# E-26_Temp_Sensor.net
KiCad netlist of a schematic drawn in Altium Designer
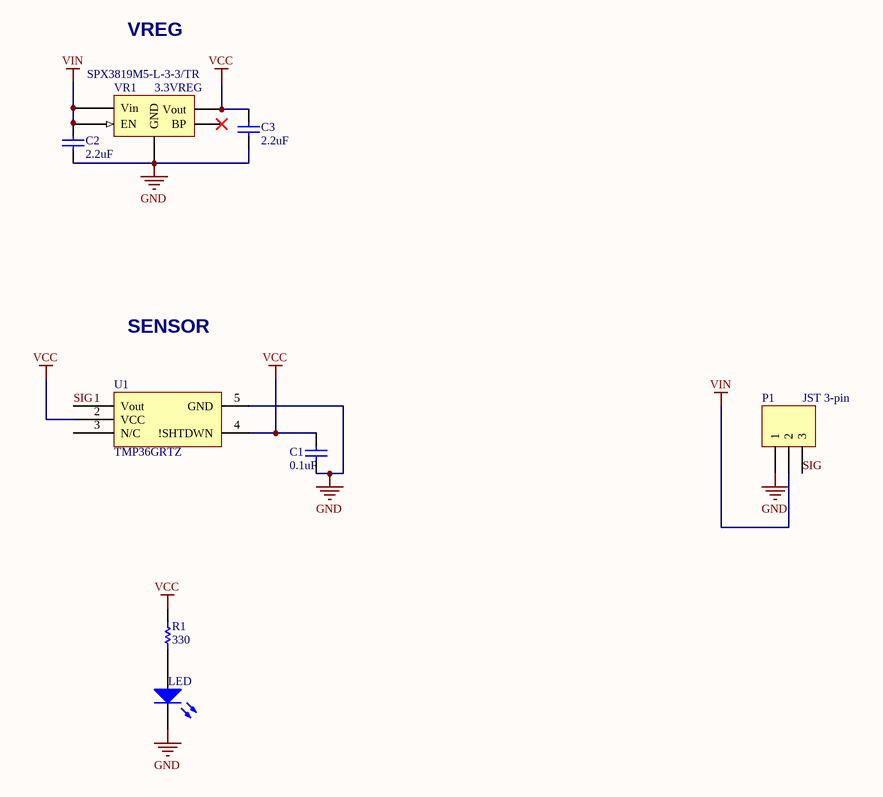
[diagram p0: E-26 Temp Sensor.SchDoc]

(export (version "E")
  (design (tool "Eeschema 10.0.6"))
  (components
    (comp (ref "C1")
      (value "0.1uF")
      (footprint "0805 TIGHT")
      (description "Capacitor")
      (fields (field (name "Comment") "18pF") (field (name "PUBLISHER") "Altium Limited"))
      (libsource (lib "SB_Discrete") (part "Cap"))
    )
    (comp (ref "C2")
      (value "2.2uF")
      (footprint "0805 TIGHT")
      (description "Capacitor")
      (fields (field (name "PUBLISHER") "Altium Limited"))
      (libsource (lib "SB_Discrete") (part "Cap"))
    )
    (comp (ref "C3")
      (value "2.2uF")
      (footprint "0805 TIGHT")
      (description "Capacitor")
      (fields (field (name "Comment") "100nF") (field (name "PUBLISHER") "Altium Limited"))
      (libsource (lib "SB_Discrete") (part "Cap"))
    )
    (comp (ref "LED")
      (value "LED2")
      (footprint "0805 LED - TIGHT")
      (description "Typical RED GaAs LED")
      (fields (field (name "PUBLISHER") "Altium Limited"))
      (libsource (lib "SB_Discrete") (part "LED1"))
    )
    (comp (ref "P1")
      (value "JST 3-pin")
      (footprint "JST-PH 3-pin SMD")
      (description "Header, 3-Pin")
      (fields (field (name "PUBLISHER") "Altium Limited"))
      (libsource (lib "Miscellaneous Connectors") (part "Header 3"))
    )
    (comp (ref "R1")
      (value "330")
      (footprint "0805 TIGHT")
      (description "Resistor")
      (fields (field (name "Comment") "Res1") (field (name "PUBLISHER") "Altium Limited"))
      (libsource (lib "SB_Discrete") (part "Res1"))
    )
    (comp (ref "U1")
      (value "TMP36GRTZ")
      (footprint "SOT-23-5")
      (libsource (lib "SB_Discrete") (part "TMP36"))
    )
    (comp (ref "VR1")
      (value "3.3VREG")
      (footprint "SOT-25 New")
      (libsource (lib "SB_Discrete") (part "Vreg SOT25"))
    )
  )
  (nets
    (net (code "1") (name "/SIG") (class "Default")
      (node (ref "P1") (pin "3") (pinfunction "3_3") (pintype "passive"))
      (node (ref "U1") (pin "1") (pinfunction "Vout_1") (pintype "power_in"))
    )
    (net (code "3") (name "GND") (class "Default")
      (node (ref "C1") (pin "1") (pinfunction "1_1") (pintype "passive"))
      (node (ref "C2") (pin "2") (pinfunction "2_2") (pintype "passive"))
      (node (ref "C3") (pin "2") (pinfunction "2_2") (pintype "passive"))
      (node (ref "LED") (pin "2") (pinfunction "K_2") (pintype "passive"))
      (node (ref "P1") (pin "1") (pinfunction "1_1") (pintype "passive"))
      (node (ref "U1") (pin "5") (pinfunction "GND_5") (pintype "power_in"))
      (node (ref "VR1") (pin "3") (pinfunction "GND_3") (pintype "passive"))
    )
    (net (code "4") (name "Net-(LED-A)") (class "Default")
      (node (ref "LED") (pin "1") (pinfunction "A_1") (pintype "passive"))
      (node (ref "R1") (pin "1") (pinfunction "1_1") (pintype "passive"))
    )
    (net (code "5") (name "VCC") (class "Default")
      (node (ref "C1") (pin "2") (pinfunction "2_2") (pintype "passive"))
      (node (ref "C3") (pin "1") (pinfunction "1_1") (pintype "passive"))
      (node (ref "R1") (pin "2") (pinfunction "2_2") (pintype "passive"))
      (node (ref "U1") (pin "2") (pinfunction "VCC_2") (pintype "power_in"))
      (node (ref "U1") (pin "4") (pinfunction "!SHTDWN_4") (pintype "power_in"))
      (node (ref "VR1") (pin "2") (pinfunction "Vout_2") (pintype "passive"))
    )
    (net (code "6") (name "VIN") (class "Default")
      (node (ref "C2") (pin "1") (pinfunction "1_1") (pintype "passive"))
      (node (ref "P1") (pin "2") (pinfunction "2_2") (pintype "passive"))
      (node (ref "VR1") (pin "4") (pinfunction "EN_4") (pintype "input"))
      (node (ref "VR1") (pin "5") (pinfunction "Vin_5") (pintype "passive"))
    )
    (net (code "7") (name "unconnected-(U1-N{slash}C-Pad3)") (class "Default")
      (node (ref "U1") (pin "3") (pinfunction "N/C_3") (pintype "passive"))
    )
    (net (code "8") (name "unconnected-(VR1-BP-Pad1)") (class "Default")
      (node (ref "VR1") (pin "1") (pinfunction "BP_1") (pintype "passive+no_connect"))
    )
  )
)
